# MotorDrive.net
KiCad netlist of a schematic drawn in Altium Designer
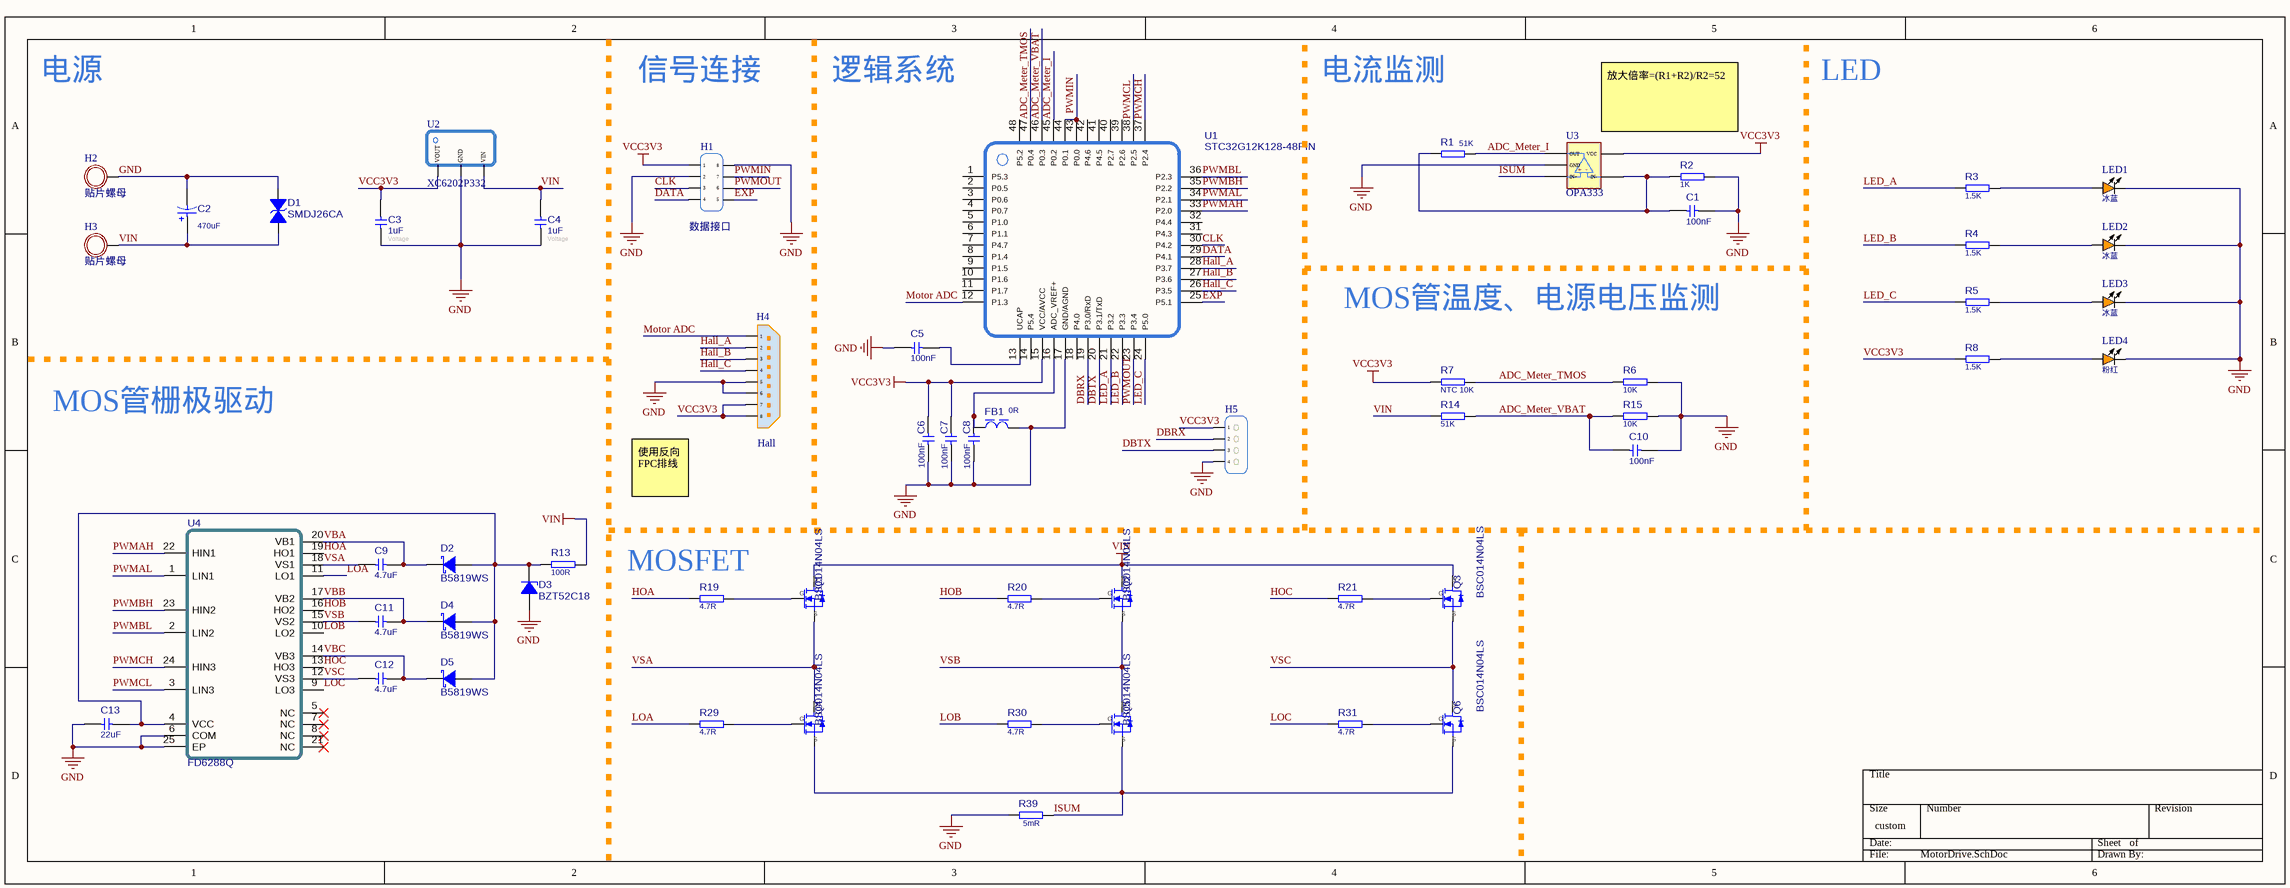
[diagram p0: MotorDrive.SchDoc]

(export (version "E")
  (design (tool "Eeschema 10.0.6"))
  (components
    (comp (ref "C1")
      (value "100nF")
      (footprint "Cap 0603_L")
      (fields (field (name "VOLTAGE") "Voltage") (field (name "Comment") "Cap-Chip"))
      (libsource (lib "GenericBase") (part "Cap-Chip"))
    )
    (comp (ref "C2")
      (value "470uF")
      (footprint "CM D(6.3*5.4)")
      (description "固态电容/电解电容/钽电容")
      (fields (field (name "VOLTAGE") "Voltage") (field (name "Comment") "极性电容"))
      (libsource (lib "GenericBase") (part "极性电容"))
    )
    (comp (ref "C3")
      (value "1uF")
      (footprint "Cap 0805_L")
      (fields (field (name "VOLTAGE") "Voltage") (field (name "Comment") "Cap-Chip"))
      (libsource (lib "GenericBase") (part "Cap-Chip"))
    )
    (comp (ref "C4")
      (value "1uF")
      (footprint "Cap 0805_L")
      (fields (field (name "VOLTAGE") "Voltage") (field (name "Comment") "Cap-Chip"))
      (libsource (lib "GenericBase") (part "Cap-Chip"))
    )
    (comp (ref "C5")
      (value "100nF")
      (footprint "Cap 0603_L")
      (fields (field (name "VOLTAGE") "Voltage") (field (name "Comment") "Cap-Chip"))
      (libsource (lib "GenericBase") (part "Cap-Chip"))
    )
    (comp (ref "C6")
      (value "100nF")
      (footprint "Cap 0603_L")
      (fields (field (name "VOLTAGE") "Voltage") (field (name "Comment") "Cap-Chip"))
      (libsource (lib "GenericBase") (part "Cap-Chip"))
    )
    (comp (ref "C7")
      (value "100nF")
      (footprint "Cap 0603_L")
      (fields (field (name "VOLTAGE") "Voltage") (field (name "Comment") "Cap-Chip"))
      (libsource (lib "GenericBase") (part "Cap-Chip"))
    )
    (comp (ref "C8")
      (value "100nF")
      (footprint "Cap 0603_L")
      (fields (field (name "VOLTAGE") "Voltage") (field (name "Comment") "Cap-Chip"))
      (libsource (lib "GenericBase") (part "Cap-Chip"))
    )
    (comp (ref "C9")
      (value "4.7uF")
      (footprint "Cap 0603_L")
      (fields (field (name "VOLTAGE") "Voltage") (field (name "Comment") "Cap-Chip"))
      (libsource (lib "GenericBase") (part "Cap-Chip"))
    )
    (comp (ref "C10")
      (value "100nF")
      (footprint "Cap 0603_L")
      (fields (field (name "VOLTAGE") "Voltage") (field (name "Comment") "Cap-Chip"))
      (libsource (lib "GenericBase") (part "Cap-Chip"))
    )
    (comp (ref "C11")
      (value "4.7uF")
      (footprint "Cap 0603_L")
      (fields (field (name "VOLTAGE") "Voltage") (field (name "Comment") "Cap-Chip"))
      (libsource (lib "GenericBase") (part "Cap-Chip"))
    )
    (comp (ref "C12")
      (value "4.7uF")
      (footprint "Cap 0603_L")
      (fields (field (name "VOLTAGE") "Voltage") (field (name "Comment") "Cap-Chip"))
      (libsource (lib "GenericBase") (part "Cap-Chip"))
    )
    (comp (ref "C13")
      (value "22uF")
      (footprint "Cap 0805_L")
      (fields (field (name "VOLTAGE") "Voltage") (field (name "Comment") "Cap-Chip"))
      (libsource (lib "GenericBase") (part "Cap-Chip"))
    )
    (comp (ref "D1")
      (value "SMDJ26CA")
      (footprint "DO-214")
      (description "TRANSIENT VOLTAGE  SUPPRESSOR DIODE")
      (fields (field (name "PUBLISHER") "Altium Limited"))
      (libsource (lib "MotorDrive") (part "Diode TVS Bi-Dir"))
    )
    (comp (ref "D2")
      (value "B5819WS")
      (footprint "SOD-323")
      (description "B5819WS 肖特基二极管")
      (libsource (lib "无刷驱动-STC-无感-Lite3S") (part "B5819WS"))
    )
    (comp (ref "D3")
      (value "BZT52C18")
      (footprint "SOD-123-L")
      (description "稳压二极管 齐纳二极管  Zener Diode")
      (fields (field (name "PUBLISHER") "Altium Limited"))
      (libsource (lib "MotorDrive") (part "BZT52C18"))
    )
    (comp (ref "D4")
      (value "B5819WS")
      (footprint "SOD-323")
      (description "B5819WS 肖特基二极管")
      (libsource (lib "无刷驱动-STC-无感-Lite3S") (part "B5819WS"))
    )
    (comp (ref "D5")
      (value "B5819WS")
      (footprint "SOD-323")
      (description "B5819WS 肖特基二极管")
      (libsource (lib "无刷驱动-STC-无感-Lite3S") (part "B5819WS"))
    )
    (comp (ref "FB1")
      (value "0R")
      (footprint "Cap 0603_L")
      (description "贴片磁珠")
      (fields (field (name "Comment") "磁珠"))
      (libsource (lib "GenericBase") (part "磁珠"))
    )
    (comp (ref "H1")
      (value "数据接口")
      (footprint "0.8mm 2X4")
      (libsource (lib "GenericBase") (part "对板连接器 2X4"))
    )
    (comp (ref "H2") (value "贴片螺母") (footprint "M4贴片螺丝") (libsource (lib "GenericBase") (part "贴片螺母")))
    (comp (ref "H3") (value "贴片螺母") (footprint "M4贴片螺丝") (libsource (lib "GenericBase") (part "贴片螺母")))
    (comp (ref "H4")
      (value "Hall")
      (footprint "FPC0.5 2H-WS-8P")
      (libsource (lib "GenericBase") (part "FPC_8Pin"))
    )
    (comp (ref "H5")
      (value "HDR 1X4")
      (footprint "HDR2.54-LI-4P")
      (libsource (lib "MotorDrive") (part "HDR 1X4"))
    )
    (comp (ref "LED1")
      (value "发光二极管")
      (footprint "LED 0603B")
      (fields (field (name "COLOR") "冰蓝"))
      (libsource (lib "GenericBase") (part "发光二极管"))
    )
    (comp (ref "LED2")
      (value "发光二极管")
      (footprint "LED 0603B")
      (fields (field (name "COLOR") "冰蓝"))
      (libsource (lib "GenericBase") (part "发光二极管"))
    )
    (comp (ref "LED3")
      (value "发光二极管")
      (footprint "LED 0603B")
      (fields (field (name "COLOR") "冰蓝"))
      (libsource (lib "GenericBase") (part "发光二极管"))
    )
    (comp (ref "LED4")
      (value "发光二极管")
      (footprint "LED 0603R")
      (fields (field (name "COLOR") "粉红"))
      (libsource (lib "GenericBase") (part "发光二极管"))
    )
    (comp (ref "Q1")
      (value "BSC014N04LS")
      (footprint "TSON3x3")
      (description "英飞凌 N沟 MOS")
      (libsource (lib "MotorDrive") (part "BSC014N04LS"))
    )
    (comp (ref "Q2")
      (value "BSC014N04LS")
      (footprint "TSON3x3")
      (description "英飞凌 N沟 MOS")
      (libsource (lib "MotorDrive") (part "BSC014N04LS"))
    )
    (comp (ref "Q3")
      (value "BSC014N04LS")
      (footprint "TSON3x3")
      (description "英飞凌 N沟 MOS")
      (libsource (lib "MotorDrive") (part "BSC014N04LS"))
    )
    (comp (ref "Q4")
      (value "BSC014N04LS")
      (footprint "TSON3x3")
      (description "英飞凌 N沟 MOS")
      (libsource (lib "MotorDrive") (part "BSC014N04LS"))
    )
    (comp (ref "Q5")
      (value "BSC014N04LS")
      (footprint "TSON3x3")
      (description "英飞凌 N沟 MOS")
      (libsource (lib "MotorDrive") (part "BSC014N04LS"))
    )
    (comp (ref "Q6")
      (value "BSC014N04LS")
      (footprint "TSON3x3")
      (description "英飞凌 N沟 MOS")
      (libsource (lib "MotorDrive") (part "BSC014N04LS"))
    )
    (comp (ref "R1")
      (value "51K")
      (footprint "Res 0603_L")
      (description "贴片电阻")
      (fields (field (name "POWER") "1/8W") (field (name "TOLERANCE") "±1%"))
      (libsource (lib "GenericBase") (part "Res-Chip"))
    )
    (comp (ref "R2")
      (value "1K")
      (footprint "Res 0603_L")
      (description "贴片电阻")
      (fields (field (name "POWER") "1/8W") (field (name "TOLERANCE") "±1%"))
      (libsource (lib "GenericBase") (part "Res-Chip"))
    )
    (comp (ref "R3")
      (value "1.5K")
      (footprint "Res 0603_L")
      (description "贴片电阻")
      (fields (field (name "POWER") "1/8W") (field (name "TOLERANCE") "±1%"))
      (libsource (lib "GenericBase") (part "Res-Chip"))
    )
    (comp (ref "R4")
      (value "1.5K")
      (footprint "Res 0603_L")
      (description "贴片电阻")
      (fields (field (name "POWER") "1/8W") (field (name "TOLERANCE") "±1%"))
      (libsource (lib "GenericBase") (part "Res-Chip"))
    )
    (comp (ref "R5")
      (value "1.5K")
      (footprint "Res 0603_L")
      (description "贴片电阻")
      (fields (field (name "POWER") "1/8W") (field (name "TOLERANCE") "±1%"))
      (libsource (lib "GenericBase") (part "Res-Chip"))
    )
    (comp (ref "R6")
      (value "10K")
      (footprint "Res 0603_L")
      (description "贴片电阻")
      (fields (field (name "POWER") "1/8W") (field (name "TOLERANCE") "±1%"))
      (libsource (lib "GenericBase") (part "Res-Chip"))
    )
    (comp (ref "R7")
      (value "NTC 10K")
      (footprint "Res 0603_L")
      (description "贴片电阻")
      (fields (field (name "POWER") "1/8W") (field (name "TOLERANCE") "±1%"))
      (libsource (lib "GenericBase") (part "Res-Chip"))
    )
    (comp (ref "R8")
      (value "1.5K")
      (footprint "Res 0603_L")
      (description "贴片电阻")
      (fields (field (name "POWER") "1/8W") (field (name "TOLERANCE") "±1%"))
      (libsource (lib "GenericBase") (part "Res-Chip"))
    )
    (comp (ref "R13")
      (value "100R")
      (footprint "Res 0805_L")
      (description "贴片电阻")
      (fields (field (name "POWER") "1/8W") (field (name "TOLERANCE") "±1%"))
      (libsource (lib "GenericBase") (part "Res-Chip"))
    )
    (comp (ref "R14")
      (value "51K")
      (footprint "Res 0603_L")
      (description "贴片电阻")
      (fields (field (name "POWER") "1/8W") (field (name "TOLERANCE") "±1%"))
      (libsource (lib "GenericBase") (part "Res-Chip"))
    )
    (comp (ref "R15")
      (value "10K")
      (footprint "Res 0603_L")
      (description "贴片电阻")
      (fields (field (name "POWER") "1/8W") (field (name "TOLERANCE") "±1%"))
      (libsource (lib "GenericBase") (part "Res-Chip"))
    )
    (comp (ref "R19")
      (value "4.7R")
      (footprint "Res 0603_L")
      (description "贴片电阻")
      (fields (field (name "POWER") "1/8W") (field (name "TOLERANCE") "±1%"))
      (libsource (lib "GenericBase") (part "Res-Chip"))
    )
    (comp (ref "R20")
      (value "4.7R")
      (footprint "Res 0603_L")
      (description "贴片电阻")
      (fields (field (name "POWER") "1/8W") (field (name "TOLERANCE") "±1%"))
      (libsource (lib "GenericBase") (part "Res-Chip"))
    )
    (comp (ref "R21")
      (value "4.7R")
      (footprint "Res 0603_L")
      (description "贴片电阻")
      (fields (field (name "POWER") "1/8W") (field (name "TOLERANCE") "±1%"))
      (libsource (lib "GenericBase") (part "Res-Chip"))
    )
    (comp (ref "R29")
      (value "4.7R")
      (footprint "Res 0603_L")
      (description "贴片电阻")
      (fields (field (name "POWER") "1/8W") (field (name "TOLERANCE") "±1%"))
      (libsource (lib "GenericBase") (part "Res-Chip"))
    )
    (comp (ref "R30")
      (value "4.7R")
      (footprint "Res 0603_L")
      (description "贴片电阻")
      (fields (field (name "POWER") "1/8W") (field (name "TOLERANCE") "±1%"))
      (libsource (lib "GenericBase") (part "Res-Chip"))
    )
    (comp (ref "R31")
      (value "4.7R")
      (footprint "Res 0603_L")
      (description "贴片电阻")
      (fields (field (name "POWER") "1/8W") (field (name "TOLERANCE") "±1%"))
      (libsource (lib "GenericBase") (part "Res-Chip"))
    )
    (comp (ref "R39")
      (value "5mR")
      (footprint "Res 2512_L")
      (description "贴片电阻")
      (fields (field (name "POWER") "1/8W") (field (name "TOLERANCE") "±1%"))
      (libsource (lib "GenericBase") (part "Res-Chip"))
    )
    (comp (ref "U1")
      (value "STC32G12K128-48PIN")
      (footprint "LQFP48 7X7_M")
      (description "STC32G12K128 LQFP48")
      (libsource (lib "MotorDrive") (part "STC32G12K128-48PIN"))
    )
    (comp (ref "U2")
      (value "XC6202P332")
      (footprint "SOT89_L")
      (description "LDO 3V3 Max=200mA")
      (libsource (lib "MotorDrive") (part "XC6202P332"))
    )
    (comp (ref "U3")
      (value "OPA333")
      (footprint "SOT23-5L")
      (libsource (lib "HardwareDebuger") (part "OPA333"))
    )
    (comp (ref "U4")
      (value "FD6288Q")
      (footprint "QFN24 4x4_M")
      (description "FD6288Q 三相栅极驱动器")
      (libsource (lib "MotorDrive") (part "FD6288Q"))
    )
  )
  (nets
    (net (code "1") (name "/ADC_Meter_I") (class "Default")
      (node (ref "R1") (pin "2") (pinfunction "2_2") (pintype "passive"))
      (node (ref "U1") (pin "45") (pinfunction "P0.2_45") (pintype "passive"))
      (node (ref "U3") (pin "1") (pinfunction "OUT_1") (pintype "passive"))
    )
    (net (code "2") (name "/ADC_Meter_TMOS") (class "Default")
      (node (ref "R6") (pin "1") (pinfunction "1_1") (pintype "passive"))
      (node (ref "R7") (pin "2") (pinfunction "2_2") (pintype "passive"))
      (node (ref "U1") (pin "47") (pinfunction "P0.4_47") (pintype "passive"))
    )
    (net (code "3") (name "/ADC_Meter_VBAT") (class "Default")
      (node (ref "C10") (pin "1") (pinfunction "1_1") (pintype "passive"))
      (node (ref "R14") (pin "2") (pinfunction "2_2") (pintype "passive"))
      (node (ref "R15") (pin "1") (pinfunction "1_1") (pintype "passive"))
      (node (ref "U1") (pin "46") (pinfunction "P0.3_46") (pintype "passive"))
    )
    (net (code "4") (name "/CLK") (class "Default")
      (node (ref "H1") (pin "3") (pinfunction "3_3") (pintype "passive"))
      (node (ref "U1") (pin "30") (pinfunction "P4.2_30") (pintype "passive"))
    )
    (net (code "5") (name "/DATA") (class "Default")
      (node (ref "H1") (pin "4") (pinfunction "4_4") (pintype "passive"))
      (node (ref "U1") (pin "29") (pinfunction "P4.1_29") (pintype "passive"))
    )
    (net (code "6") (name "/DBRX") (class "Default")
      (node (ref "H5") (pin "2") (pinfunction "2_2") (pintype "passive"))
      (node (ref "U1") (pin "19") (pinfunction "P3.0/RxD_19") (pintype "passive"))
    )
    (net (code "7") (name "/DBTX") (class "Default")
      (node (ref "H5") (pin "3") (pinfunction "3_3") (pintype "passive"))
      (node (ref "U1") (pin "20") (pinfunction "P3.1/TxD_20") (pintype "passive"))
    )
    (net (code "8") (name "/EXP") (class "Default")
      (node (ref "H1") (pin "5") (pinfunction "5_5") (pintype "passive"))
      (node (ref "U1") (pin "25") (pinfunction "P5.1_25") (pintype "passive"))
    )
    (net (code "9") (name "/HOA") (class "Default")
      (node (ref "R19") (pin "1") (pinfunction "1_1") (pintype "passive"))
      (node (ref "U4") (pin "19") (pinfunction "HO1_19") (pintype "passive"))
    )
    (net (code "10") (name "/HOB") (class "Default")
      (node (ref "R20") (pin "1") (pinfunction "1_1") (pintype "passive"))
      (node (ref "U4") (pin "16") (pinfunction "HO2_16") (pintype "passive"))
    )
    (net (code "11") (name "/HOC") (class "Default")
      (node (ref "R21") (pin "1") (pinfunction "1_1") (pintype "passive"))
      (node (ref "U4") (pin "13") (pinfunction "HO3_13") (pintype "passive"))
    )
    (net (code "12") (name "/Hall_A") (class "Default")
      (node (ref "H4") (pin "2") (pinfunction "2_2") (pintype "passive"))
      (node (ref "U1") (pin "28") (pinfunction "P3.7_28") (pintype "passive"))
    )
    (net (code "13") (name "/Hall_B") (class "Default")
      (node (ref "H4") (pin "3") (pinfunction "3_3") (pintype "passive"))
      (node (ref "U1") (pin "27") (pinfunction "P3.6_27") (pintype "passive"))
    )
    (net (code "14") (name "/Hall_C") (class "Default")
      (node (ref "H4") (pin "4") (pinfunction "4_4") (pintype "passive"))
      (node (ref "U1") (pin "26") (pinfunction "P3.5_26") (pintype "passive"))
    )
    (net (code "15") (name "/ISUM") (class "Default")
      (node (ref "Q4") (pin "3") (pinfunction "S_3") (pintype "passive"))
      (node (ref "Q5") (pin "3") (pinfunction "S_3") (pintype "passive"))
      (node (ref "Q6") (pin "3") (pinfunction "S_3") (pintype "passive"))
      (node (ref "R39") (pin "2") (pinfunction "2_2") (pintype "passive"))
      (node (ref "U3") (pin "3") (pinfunction "IN+_3") (pintype "passive"))
    )
    (net (code "16") (name "/LED_A") (class "Default")
      (node (ref "R3") (pin "1") (pinfunction "1_1") (pintype "passive"))
      (node (ref "U1") (pin "21") (pinfunction "P3.2_21") (pintype "passive"))
    )
    (net (code "17") (name "/LED_B") (class "Default")
      (node (ref "R4") (pin "1") (pinfunction "1_1") (pintype "passive"))
      (node (ref "U1") (pin "22") (pinfunction "P3.3_22") (pintype "passive"))
    )
    (net (code "18") (name "/LED_C") (class "Default")
      (node (ref "R5") (pin "1") (pinfunction "1_1") (pintype "passive"))
      (node (ref "U1") (pin "24") (pinfunction "P5.0_24") (pintype "passive"))
    )
    (net (code "19") (name "/LOA") (class "Default")
      (node (ref "R29") (pin "1") (pinfunction "1_1") (pintype "passive"))
      (node (ref "U4") (pin "11") (pinfunction "LO1_11") (pintype "passive"))
    )
    (net (code "20") (name "/LOB") (class "Default")
      (node (ref "R30") (pin "1") (pinfunction "1_1") (pintype "passive"))
      (node (ref "U4") (pin "10") (pinfunction "LO2_10") (pintype "passive"))
    )
    (net (code "21") (name "/LOC") (class "Default")
      (node (ref "R31") (pin "1") (pinfunction "1_1") (pintype "passive"))
      (node (ref "U4") (pin "9") (pinfunction "LO3_9") (pintype "passive"))
    )
    (net (code "22") (name "/Motor ADC") (class "Default")
      (node (ref "H4") (pin "1") (pinfunction "1_1") (pintype "passive"))
      (node (ref "U1") (pin "12") (pinfunction "P1.3_12") (pintype "passive"))
    )
    (net (code "23") (name "/PWMAH") (class "Default")
      (node (ref "U1") (pin "33") (pinfunction "P2.0_33") (pintype "passive"))
      (node (ref "U4") (pin "22") (pinfunction "HIN1_22") (pintype "passive"))
    )
    (net (code "24") (name "/PWMAL") (class "Default")
      (node (ref "U1") (pin "34") (pinfunction "P2.1_34") (pintype "passive"))
      (node (ref "U4") (pin "1") (pinfunction "LIN1_1") (pintype "passive"))
    )
    (net (code "25") (name "/PWMBH") (class "Default")
      (node (ref "U1") (pin "35") (pinfunction "P2.2_35") (pintype "passive"))
      (node (ref "U4") (pin "23") (pinfunction "HIN2_23") (pintype "passive"))
    )
    (net (code "26") (name "/PWMBL") (class "Default")
      (node (ref "U1") (pin "36") (pinfunction "P2.3_36") (pintype "passive"))
      (node (ref "U4") (pin "2") (pinfunction "LIN2_2") (pintype "passive"))
    )
    (net (code "27") (name "/PWMCH") (class "Default")
      (node (ref "U1") (pin "37") (pinfunction "P2.4_37") (pintype "passive"))
      (node (ref "U4") (pin "24") (pinfunction "HIN3_24") (pintype "passive"))
    )
    (net (code "28") (name "/PWMCL") (class "Default")
      (node (ref "U1") (pin "38") (pinfunction "P2.5_38") (pintype "passive"))
      (node (ref "U4") (pin "3") (pinfunction "LIN3_3") (pintype "passive"))
    )
    (net (code "29") (name "/PWMIN") (class "Default")
      (node (ref "H1") (pin "7") (pinfunction "7_7") (pintype "passive"))
      (node (ref "U1") (pin "43") (pinfunction "P0.0_43") (pintype "passive"))
      (node (ref "U1") (pin "44") (pinfunction "P0.1_44") (pintype "passive"))
    )
    (net (code "30") (name "/PWMOUT") (class "Default")
      (node (ref "H1") (pin "6") (pinfunction "6_6") (pintype "passive"))
      (node (ref "U1") (pin "23") (pinfunction "P3.4_23") (pintype "passive"))
    )
    (net (code "31") (name "/VBA") (class "Default")
      (node (ref "C9") (pin "2") (pinfunction "2_2") (pintype "passive"))
      (node (ref "D2") (pin "K") (pinfunction "K_K") (pintype "passive"))
      (node (ref "U4") (pin "20") (pinfunction "VB1_20") (pintype "passive"))
    )
    (net (code "32") (name "/VBB") (class "Default")
      (node (ref "C11") (pin "2") (pinfunction "2_2") (pintype "passive"))
      (node (ref "D4") (pin "K") (pinfunction "K_K") (pintype "passive"))
      (node (ref "U4") (pin "17") (pinfunction "VB2_17") (pintype "passive"))
    )
    (net (code "33") (name "/VBC") (class "Default")
      (node (ref "C12") (pin "2") (pinfunction "2_2") (pintype "passive"))
      (node (ref "D5") (pin "K") (pinfunction "K_K") (pintype "passive"))
      (node (ref "U4") (pin "14") (pinfunction "VB3_14") (pintype "passive"))
    )
    (net (code "34") (name "/VSA") (class "Default")
      (node (ref "C9") (pin "1") (pinfunction "1_1") (pintype "passive"))
      (node (ref "Q1") (pin "3") (pinfunction "S_3") (pintype "passive"))
      (node (ref "Q4") (pin "1") (pinfunction "D_1") (pintype "passive"))
      (node (ref "U4") (pin "18") (pinfunction "VS1_18") (pintype "passive"))
    )
    (net (code "35") (name "/VSB") (class "Default")
      (node (ref "C11") (pin "1") (pinfunction "1_1") (pintype "passive"))
      (node (ref "Q2") (pin "3") (pinfunction "S_3") (pintype "passive"))
      (node (ref "Q5") (pin "1") (pinfunction "D_1") (pintype "passive"))
      (node (ref "U4") (pin "15") (pinfunction "VS2_15") (pintype "passive"))
    )
    (net (code "36") (name "/VSC") (class "Default")
      (node (ref "C12") (pin "1") (pinfunction "1_1") (pintype "passive"))
      (node (ref "Q3") (pin "3") (pinfunction "S_3") (pintype "passive"))
      (node (ref "Q6") (pin "1") (pinfunction "D_1") (pintype "passive"))
      (node (ref "U4") (pin "12") (pinfunction "VS3_12") (pintype "passive"))
    )
    (net (code "37") (name "GND") (class "Default")
      (node (ref "C1") (pin "2") (pinfunction "2_2") (pintype "passive"))
      (node (ref "C10") (pin "2") (pinfunction "2_2") (pintype "passive"))
      (node (ref "C13") (pin "1") (pinfunction "1_1") (pintype "passive"))
      (node (ref "C2") (pin "2") (pinfunction "2_2") (pintype "passive"))
      (node (ref "C3") (pin "1") (pinfunction "1_1") (pintype "passive"))
      (node (ref "C4") (pin "1") (pinfunction "1_1") (pintype "passive"))
      (node (ref "C5") (pin "1") (pinfunction "1_1") (pintype "passive"))
      (node (ref "C6") (pin "1") (pinfunction "1_1") (pintype "passive"))
      (node (ref "C7") (pin "1") (pinfunction "1_1") (pintype "passive"))
      (node (ref "C8") (pin "1") (pinfunction "1_1") (pintype "passive"))
      (node (ref "D1") (pin "1") (pinfunction "1_1") (pintype "passive"))
      (node (ref "D3") (pin "A") (pinfunction "A_A") (pintype "passive"))
      (node (ref "FB1") (pin "2") (pinfunction "2_2") (pintype "passive"))
      (node (ref "H1") (pin "2") (pinfunction "2_2") (pintype "passive"))
      (node (ref "H1") (pin "8") (pinfunction "8_8") (pintype "passive"))
      (node (ref "H2") (pin "1") (pinfunction "1_1") (pintype "passive"))
      (node (ref "H4") (pin "5") (pinfunction "5_5") (pintype "passive"))
      (node (ref "H4") (pin "6") (pinfunction "6_6") (pintype "passive"))
      (node (ref "H5") (pin "4") (pinfunction "4_4") (pintype "passive"))
      (node (ref "LED1") (pin "2") (pinfunction "K_2") (pintype "passive"))
      (node (ref "LED2") (pin "2") (pinfunction "K_2") (pintype "passive"))
      (node (ref "LED3") (pin "2") (pinfunction "K_2") (pintype "passive"))
      (node (ref "LED4") (pin "2") (pinfunction "K_2") (pintype "passive"))
      (node (ref "R15") (pin "2") (pinfunction "2_2") (pintype "passive"))
      (node (ref "R2") (pin "2") (pinfunction "2_2") (pintype "passive"))
      (node (ref "R39") (pin "1") (pinfunction "1_1") (pintype "passive"))
      (node (ref "R6") (pin "2") (pinfunction "2_2") (pintype "passive"))
      (node (ref "U1") (pin "17") (pinfunction "GND/AGND_17") (pintype "passive"))
      (node (ref "U2") (pin "2") (pinfunction "GND_2") (pintype "passive"))
      (node (ref "U3") (pin "2") (pinfunction "GND_2") (pintype "passive"))
      (node (ref "U4") (pin "25") (pinfunction "EP_25") (pintype "passive"))
      (node (ref "U4") (pin "6") (pinfunction "COM_6") (pintype "passive"))
    )
    (net (code "38") (name "Net-(LED1-A)") (class "Default")
      (node (ref "LED1") (pin "1") (pinfunction "A_1") (pintype "passive"))
      (node (ref "R3") (pin "2") (pinfunction "2_2") (pintype "passive"))
    )
    (net (code "39") (name "Net-(LED2-A)") (class "Default")
      (node (ref "LED2") (pin "1") (pinfunction "A_1") (pintype "passive"))
      (node (ref "R4") (pin "2") (pinfunction "2_2") (pintype "passive"))
    )
    (net (code "40") (name "Net-(LED3-A)") (class "Default")
      (node (ref "LED3") (pin "1") (pinfunction "A_1") (pintype "passive"))
      (node (ref "R5") (pin "2") (pinfunction "2_2") (pintype "passive"))
    )
    (net (code "41") (name "Net-(LED4-A)") (class "Default")
      (node (ref "LED4") (pin "1") (pinfunction "A_1") (pintype "passive"))
      (node (ref "R8") (pin "2") (pinfunction "2_2") (pintype "passive"))
    )
    (net (code "42") (name "Net-(Q1-G)") (class "Default")
      (node (ref "Q1") (pin "2") (pinfunction "G_2") (pintype "passive"))
      (node (ref "R19") (pin "2") (pinfunction "2_2") (pintype "passive"))
    )
    (net (code "43") (name "Net-(Q2-G)") (class "Default")
      (node (ref "Q2") (pin "2") (pinfunction "G_2") (pintype "passive"))
      (node (ref "R20") (pin "2") (pinfunction "2_2") (pintype "passive"))
    )
    (net (code "44") (name "Net-(Q3-G)") (class "Default")
      (node (ref "Q3") (pin "2") (pinfunction "G_2") (pintype "passive"))
      (node (ref "R21") (pin "2") (pinfunction "2_2") (pintype "passive"))
    )
    (net (code "45") (name "Net-(Q4-G)") (class "Default")
      (node (ref "Q4") (pin "2") (pinfunction "G_2") (pintype "passive"))
      (node (ref "R29") (pin "2") (pinfunction "2_2") (pintype "passive"))
    )
    (net (code "46") (name "Net-(Q5-G)") (class "Default")
      (node (ref "Q5") (pin "2") (pinfunction "G_2") (pintype "passive"))
      (node (ref "R30") (pin "2") (pinfunction "2_2") (pintype "passive"))
    )
    (net (code "47") (name "Net-(Q6-G)") (class "Default")
      (node (ref "Q6") (pin "2") (pinfunction "G_2") (pintype "passive"))
      (node (ref "R31") (pin "2") (pinfunction "2_2") (pintype "passive"))
    )
    (net (code "48") (name "Net-(U1-ADC_VREF+)") (class "Default")
      (node (ref "C8") (pin "2") (pinfunction "2_2") (pintype "passive"))
      (node (ref "FB1") (pin "1") (pinfunction "1_1") (pintype "passive"))
      (node (ref "U1") (pin "16") (pinfunction "ADC_VREF+_16") (pintype "passive"))
    )
    (net (code "49") (name "Net-(U1-UCAP)") (class "Default")
      (node (ref "C5") (pin "2") (pinfunction "2_2") (pintype "passive"))
      (node (ref "U1") (pin "13") (pinfunction "UCAP_13") (pintype "passive"))
    )
    (net (code "50") (name "Net-(U3-IN-)") (class "Default")
      (node (ref "C1") (pin "1") (pinfunction "1_1") (pintype "passive"))
      (node (ref "R1") (pin "1") (pinfunction "1_1") (pintype "passive"))
      (node (ref "R2") (pin "1") (pinfunction "1_1") (pintype "passive"))
      (node (ref "U3") (pin "4") (pinfunction "IN-_4") (pintype "passive"))
    )
    (net (code "51") (name "Net-(U4-VCC)") (class "Default")
      (node (ref "C13") (pin "2") (pinfunction "2_2") (pintype "passive"))
      (node (ref "D2") (pin "A") (pinfunction "A_A") (pintype "passive"))
      (node (ref "D3") (pin "K") (pinfunction "K_K") (pintype "passive"))
      (node (ref "D4") (pin "A") (pinfunction "A_A") (pintype "passive"))
      (node (ref "D5") (pin "A") (pinfunction "A_A") (pintype "passive"))
      (node (ref "R13") (pin "1") (pinfunction "1_1") (pintype "passive"))
      (node (ref "U4") (pin "4") (pinfunction "VCC_4") (pintype "passive"))
    )
    (net (code "52") (name "VCC3V3") (class "Default")
      (node (ref "C3") (pin "2") (pinfunction "2_2") (pintype "passive"))
      (node (ref "C6") (pin "2") (pinfunction "2_2") (pintype "passive"))
      (node (ref "C7") (pin "2") (pinfunction "2_2") (pintype "passive"))
      (node (ref "H1") (pin "1") (pinfunction "1_1") (pintype "passive"))
      (node (ref "H4") (pin "7") (pinfunction "7_7") (pintype "passive"))
      (node (ref "H4") (pin "8") (pinfunction "8_8") (pintype "passive"))
      (node (ref "H5") (pin "1") (pinfunction "1_1") (pintype "passive"))
      (node (ref "R7") (pin "1") (pinfunction "1_1") (pintype "passive"))
      (node (ref "R8") (pin "1") (pinfunction "1_1") (pintype "passive"))
      (node (ref "U1") (pin "15") (pinfunction "VCC/AVCC_15") (pintype "passive"))
      (node (ref "U2") (pin "1") (pinfunction "VOUT_1") (pintype "passive"))
      (node (ref "U3") (pin "5") (pinfunction "VCC_5") (pintype "passive"))
    )
    (net (code "53") (name "VIN") (class "Default")
      (node (ref "C2") (pin "1") (pinfunction "1_1") (pintype "passive"))
      (node (ref "C4") (pin "2") (pinfunction "2_2") (pintype "passive"))
      (node (ref "D1") (pin "2") (pinfunction "2_2") (pintype "passive"))
      (node (ref "H3") (pin "1") (pinfunction "1_1") (pintype "passive"))
      (node (ref "Q1") (pin "1") (pinfunction "D_1") (pintype "passive"))
      (node (ref "Q2") (pin "1") (pinfunction "D_1") (pintype "passive"))
      (node (ref "Q3") (pin "1") (pinfunction "D_1") (pintype "passive"))
      (node (ref "R13") (pin "2") (pinfunction "2_2") (pintype "passive"))
      (node (ref "R14") (pin "1") (pinfunction "1_1") (pintype "passive"))
      (node (ref "U2") (pin "3") (pinfunction "VIN_3") (pintype "passive"))
    )
    (net (code "54") (name "unconnected-(U1-P0.5-Pad2)") (class "Default")
      (node (ref "U1") (pin "2") (pinfunction "P0.5_2") (pintype "passive"))
    )
    (net (code "55") (name "unconnected-(U1-P0.6-Pad3)") (class "Default")
      (node (ref "U1") (pin "3") (pinfunction "P0.6_3") (pintype "passive"))
    )
    (net (code "56") (name "unconnected-(U1-P0.7-Pad4)") (class "Default")
      (node (ref "U1") (pin "4") (pinfunction "P0.7_4") (pintype "passive"))
    )
    (net (code "57") (name "unconnected-(U1-P1.0-Pad5)") (class "Default")
      (node (ref "U1") (pin "5") (pinfunction "P1.0_5") (pintype "passive"))
    )
    (net (code "58") (name "unconnected-(U1-P1.1-Pad6)") (class "Default")
      (node (ref "U1") (pin "6") (pinfunction "P1.1_6") (pintype "passive"))
    )
    (net (code "59") (name "unconnected-(U1-P1.4-Pad8)") (class "Default")
      (node (ref "U1") (pin "8") (pinfunction "P1.4_8") (pintype "passive"))
    )
    (net (code "60") (name "unconnected-(U1-P1.5-Pad9)") (class "Default")
      (node (ref "U1") (pin "9") (pinfunction "P1.5_9") (pintype "passive"))
    )
    (net (code "61") (name "unconnected-(U1-P1.6-Pad10)") (class "Default")
      (node (ref "U1") (pin "10") (pinfunction "P1.6_10") (pintype "passive"))
    )
    (net (code "62") (name "unconnected-(U1-P1.7-Pad11)") (class "Default")
      (node (ref "U1") (pin "11") (pinfunction "P1.7_11") (pintype "passive"))
    )
    (net (code "63") (name "unconnected-(U1-P2.6-Pad39)") (class "Default")
      (node (ref "U1") (pin "39") (pinfunction "P2.6_39") (pintype "passive"))
    )
    (net (code "64") (name "unconnected-(U1-P2.7-Pad40)") (class "Default")
      (node (ref "U1") (pin "40") (pinfunction "P2.7_40") (pintype "passive"))
    )
    (net (code "65") (name "unconnected-(U1-P4.0-Pad18)") (class "Default")
      (node (ref "U1") (pin "18") (pinfunction "P4.0_18") (pintype "passive"))
    )
    (net (code "66") (name "unconnected-(U1-P4.3-Pad31)") (class "Default")
      (node (ref "U1") (pin "31") (pinfunction "P4.3_31") (pintype "passive"))
    )
    (net (code "67") (name "unconnected-(U1-P4.4-Pad32)") (class "Default")
      (node (ref "U1") (pin "32") (pinfunction "P4.4_32") (pintype "passive"))
    )
    (net (code "68") (name "unconnected-(U1-P4.5-Pad41)") (class "Default")
      (node (ref "U1") (pin "41") (pinfunction "P4.5_41") (pintype "passive"))
    )
    (net (code "69") (name "unconnected-(U1-P4.6-Pad42)") (class "Default")
      (node (ref "U1") (pin "42") (pinfunction "P4.6_42") (pintype "passive"))
    )
    (net (code "70") (name "unconnected-(U1-P4.7-Pad7)") (class "Default")
      (node (ref "U1") (pin "7") (pinfunction "P4.7_7") (pintype "passive"))
    )
    (net (code "71") (name "unconnected-(U1-P5.2-Pad48)") (class "Default")
      (node (ref "U1") (pin "48") (pinfunction "P5.2_48") (pintype "passive"))
    )
    (net (code "72") (name "unconnected-(U1-P5.3-Pad1)") (class "Default")
      (node (ref "U1") (pin "1") (pinfunction "P5.3_1") (pintype "passive"))
    )
    (net (code "73") (name "unconnected-(U1-P5.4-Pad14)") (class "Default")
      (node (ref "U1") (pin "14") (pinfunction "P5.4_14") (pintype "passive"))
    )
    (net (code "74") (name "unconnected-(U4-NC-Pad5)") (class "Default")
      (node (ref "U4") (pin "5") (pinfunction "NC_5") (pintype "passive+no_connect"))
    )
    (net (code "75") (name "unconnected-(U4-NC-Pad7)") (class "Default")
      (node (ref "U4") (pin "7") (pinfunction "NC_7") (pintype "passive+no_connect"))
    )
    (net (code "76") (name "unconnected-(U4-NC-Pad8)") (class "Default")
      (node (ref "U4") (pin "8") (pinfunction "NC_8") (pintype "passive+no_connect"))
    )
    (net (code "77") (name "unconnected-(U4-NC-Pad21)") (class "Default")
      (node (ref "U4") (pin "21") (pinfunction "NC_21") (pintype "passive+no_connect"))
    )
  )
)
